# schematic.net
KiCad netlist of a schematic drawn in EasyEDA
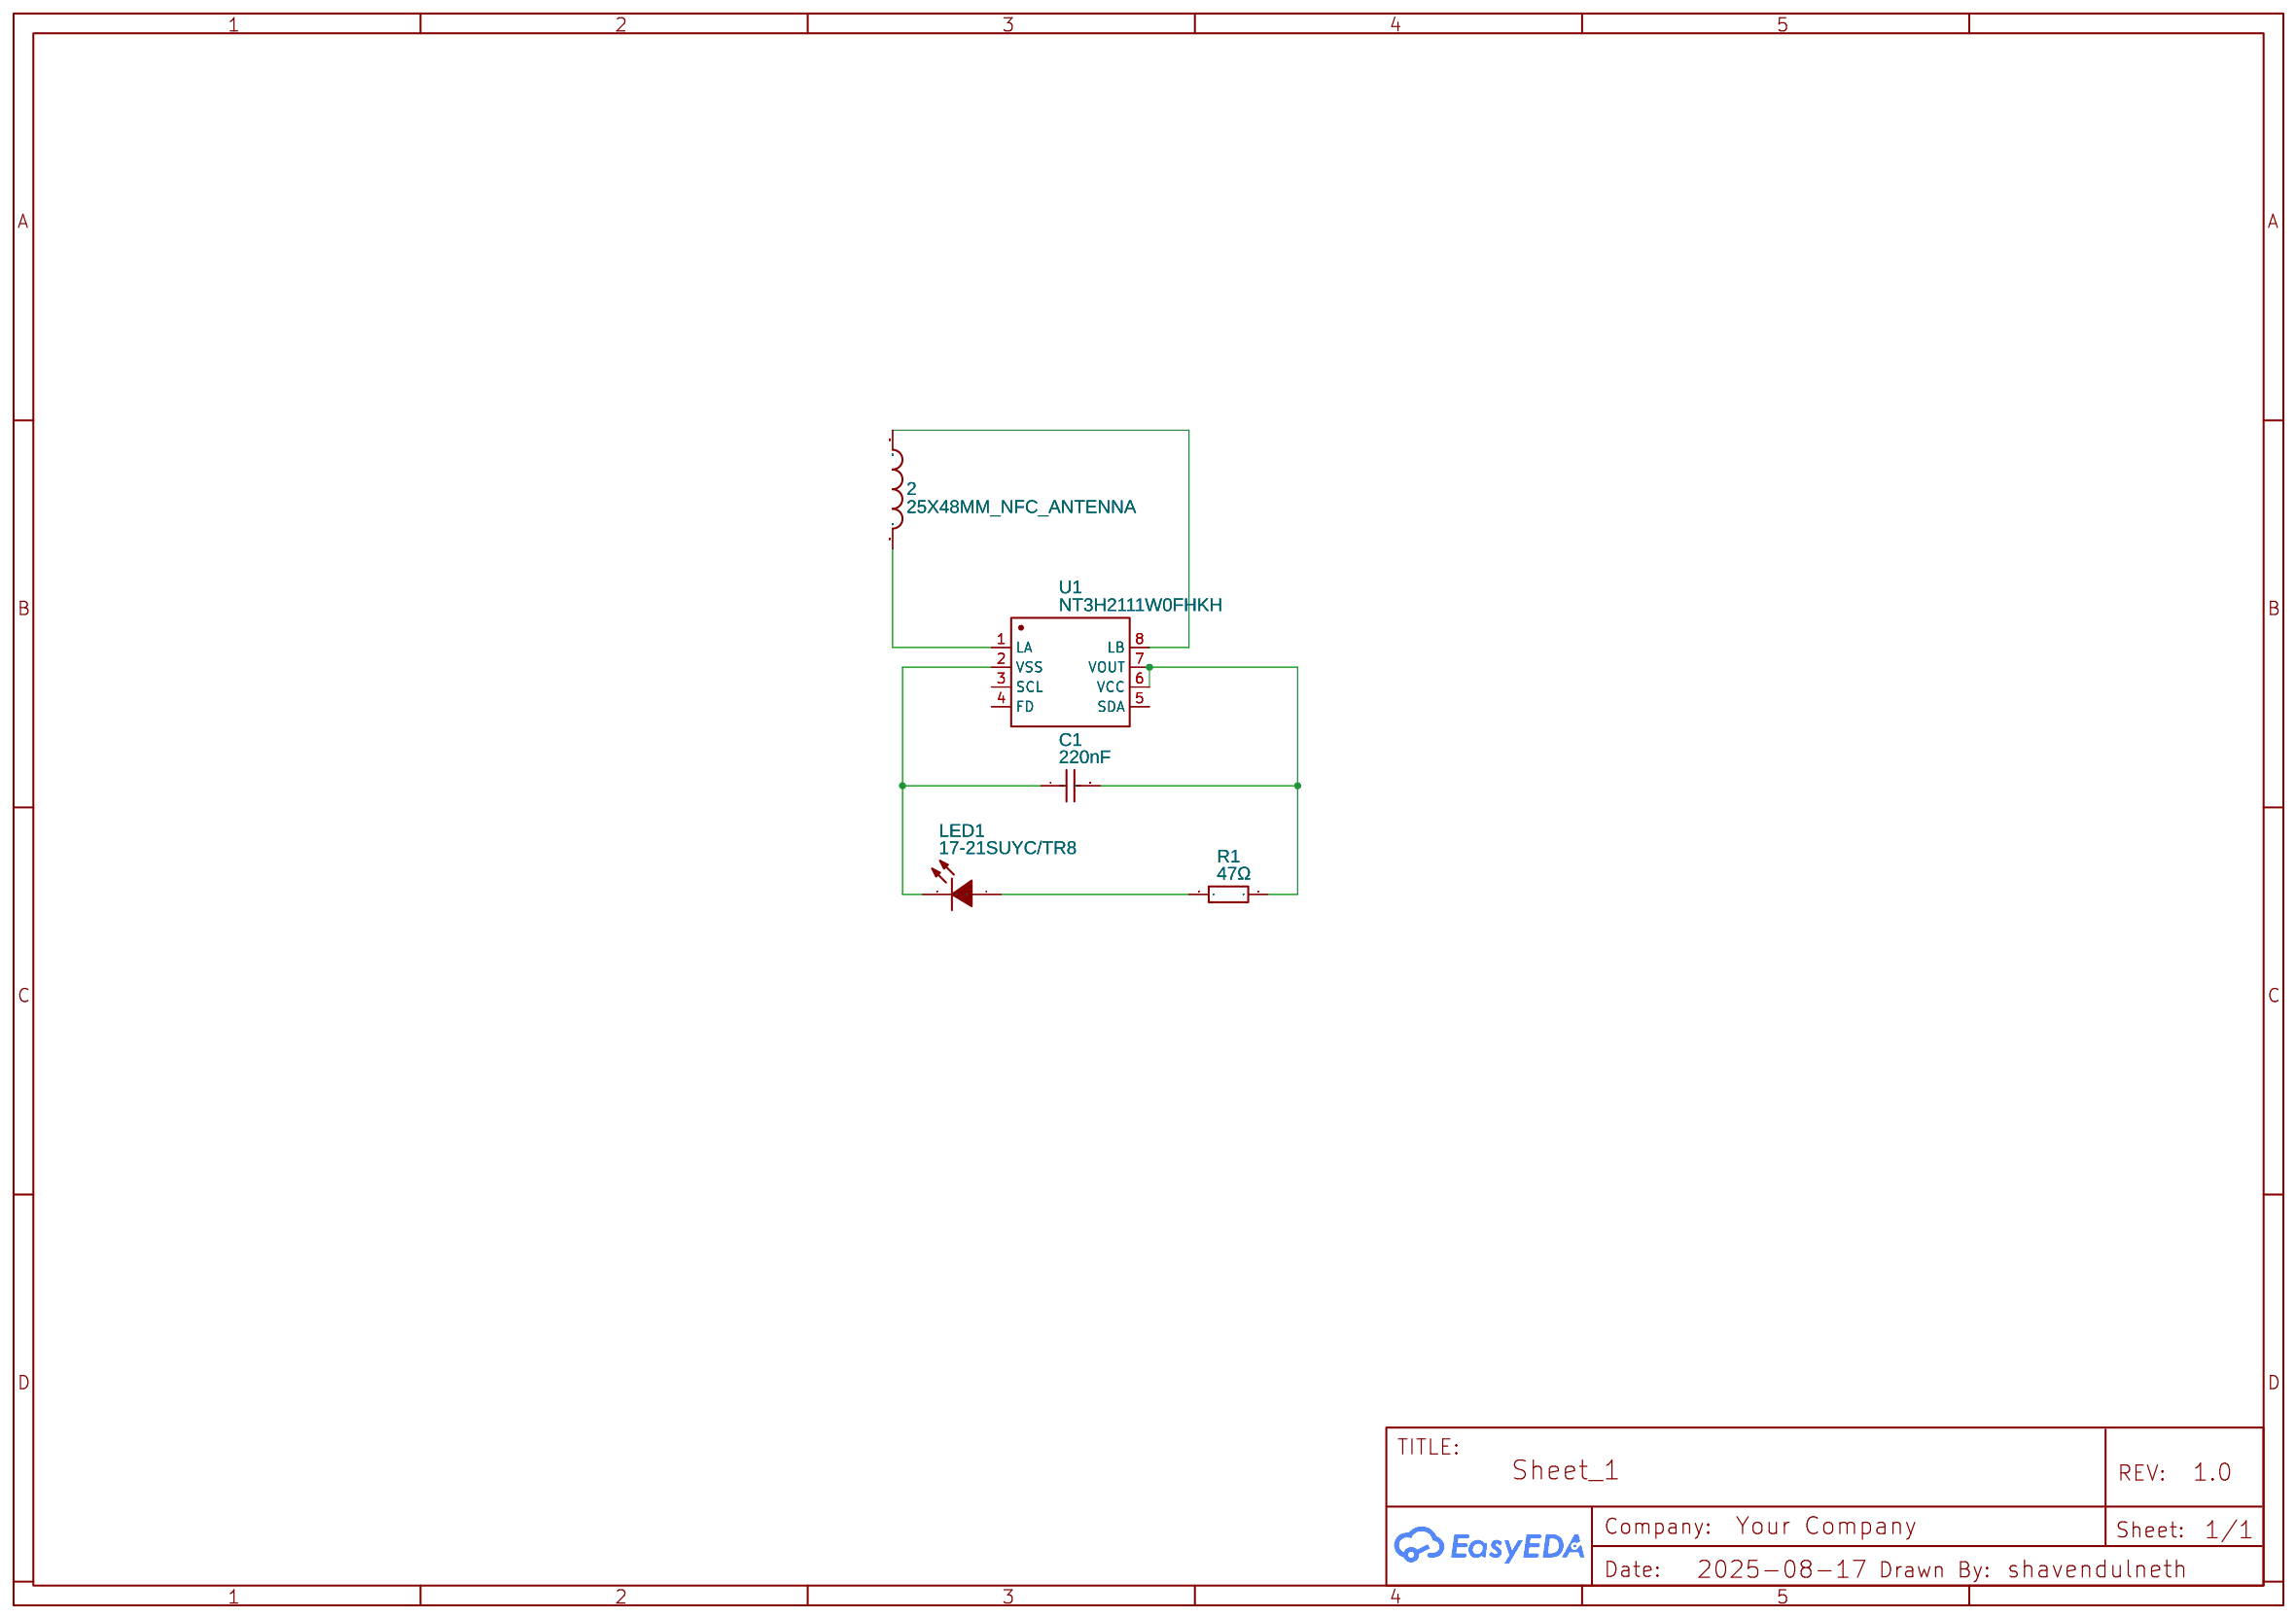
[diagram p0: schematic sheet]

(export (version "E")
  (design (tool "Eeschema 10.0.6"))
  (components
    (comp (ref "2") (value "25X48MM_NFC_ANTENNA") (libsource (lib "") (part "25X48MM_NFC_ANTENNA")))
    (comp (ref "C1")
      (value "220nF")
      (fields
        (field (name "Manufacturer Part") "CL10B224KA8NNNC")
        (field (name "Manufacturer") "SAMSUNG(三星)")
      )
      (libsource (lib "") (part "CL10B224KA8NNNC"))
    )
    (comp (ref "LED1")
      (value "17-21SUYC/TR8")
      (fields (field (name "Manufacturer Part") "KT-0805黄灯") (field (name "Manufacturer") "KENTO"))
      (libsource (lib "") (part "17-21SUYC/TR8"))
    )
    (comp (ref "R1")
      (value "47Ω")
      (fields
        (field (name "Manufacturer Part") "0603WAF470JT5E")
        (field (name "Manufacturer") "UNI-ROYAL(厚声)")
      )
      (libsource (lib "") (part "0603WAF470JT5E"))
    )
    (comp (ref "U1")
      (value "NT3H2111W0FHKH")
      (fields (field (name "Manufacturer") "NXP(恩智浦)"))
      (libsource (lib "") (part "NT3H2111W0FHKH"))
    )
  )
  (nets
    (net (code "1") (name "Net-(LED1-+)") (class "Default")
      (node (ref "LED1") (pin "1") (pinfunction "+_1") (pintype "unspecified"))
      (node (ref "R1") (pin "1") (pinfunction "1_1") (pintype "input"))
    )
    (net (code "2") (name "Net-(LED1--)") (class "Default")
      (node (ref "C1") (pin "1") (pinfunction "1_1") (pintype "input"))
      (node (ref "LED1") (pin "2") (pinfunction "-_2") (pintype "unspecified"))
      (node (ref "U1") (pin "2") (pinfunction "VSS_2") (pintype "unspecified"))
    )
    (net (code "3") (name "Net-(U1-LA)") (class "Default")
      (node (ref "2") (pin "P$2") (pinfunction "P$2_P$2") (pintype "bidirectional"))
      (node (ref "U1") (pin "1") (pinfunction "LA_1") (pintype "unspecified"))
    )
    (net (code "4") (name "Net-(U1-LB)") (class "Default")
      (node (ref "2") (pin "P$1") (pinfunction "P$1_P$1") (pintype "bidirectional"))
      (node (ref "U1") (pin "8") (pinfunction "LB_8") (pintype "unspecified"))
    )
    (net (code "5") (name "Net-(U1-VCC)") (class "Default")
      (node (ref "C1") (pin "2") (pinfunction "2_2") (pintype "input"))
      (node (ref "R1") (pin "2") (pinfunction "2_2") (pintype "input"))
      (node (ref "U1") (pin "6") (pinfunction "VCC_6") (pintype "unspecified"))
      (node (ref "U1") (pin "7") (pinfunction "VOUT_7") (pintype "unspecified"))
    )
    (net (code "6") (name "unconnected-(U1-FD-Pad4)") (class "Default")
      (node (ref "U1") (pin "4") (pinfunction "FD_4") (pintype "unspecified"))
    )
    (net (code "7") (name "unconnected-(U1-SCL-Pad3)") (class "Default")
      (node (ref "U1") (pin "3") (pinfunction "SCL_3") (pintype "unspecified"))
    )
    (net (code "8") (name "unconnected-(U1-SDA-Pad5)") (class "Default")
      (node (ref "U1") (pin "5") (pinfunction "SDA_5") (pintype "unspecified"))
    )
  )
)
